# usb-rs485.net
KiCad netlist of a schematic drawn in EAGLE
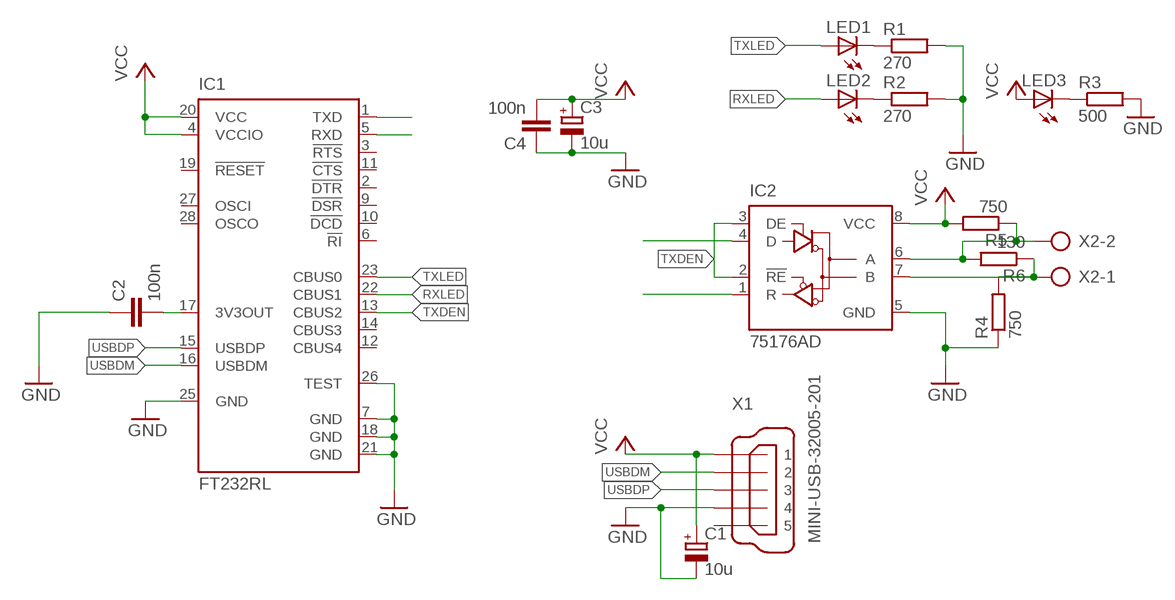
[diagram p0: schematic, sheet 1]

(export (version "E")
  (design (tool "Eeschema 10.0.6"))
  (components
    (comp (ref "C1")
      (value "10u")
      (footprint "eagle-import:PANASONIC_D")
      (libsource (lib "eagle-import") (part "CPOL-EUD"))
    )
    (comp (ref "C2")
      (value "100n")
      (footprint "eagle-import:C0805")
      (libsource (lib "eagle-import") (part "C-EUC0805"))
    )
    (comp (ref "C3")
      (value "10u")
      (footprint "eagle-import:PANASONIC_D")
      (libsource (lib "eagle-import") (part "CPOL-EUD"))
    )
    (comp (ref "C4")
      (value "100n")
      (footprint "eagle-import:C0805")
      (libsource (lib "eagle-import") (part "C-EUC0805"))
    )
    (comp (ref "IC1")
      (value "FT232RL")
      (footprint "eagle-import:SSOP28")
      (libsource (lib "eagle-import") (part "FT232RL"))
    )
    (comp (ref "IC2")
      (value "75176AD")
      (footprint "eagle-import:D_R-PDSO-G8")
      (libsource (lib "eagle-import") (part "75176AD"))
    )
    (comp (ref "LED1")
      (value "LEDSML0805")
      (footprint "eagle-import:SML0805")
      (libsource (lib "eagle-import") (part "LEDSML0805"))
    )
    (comp (ref "LED2")
      (value "LEDSML0805")
      (footprint "eagle-import:SML0805")
      (libsource (lib "eagle-import") (part "LEDSML0805"))
    )
    (comp (ref "LED3")
      (value "LEDSML0805")
      (footprint "eagle-import:SML0805")
      (libsource (lib "eagle-import") (part "LEDSML0805"))
    )
    (comp (ref "R1")
      (value "270")
      (footprint "eagle-import:R0805")
      (libsource (lib "eagle-import") (part "R-EU_R0805"))
    )
    (comp (ref "R2")
      (value "270")
      (footprint "eagle-import:R0805")
      (libsource (lib "eagle-import") (part "R-EU_R0805"))
    )
    (comp (ref "R3")
      (value "500")
      (footprint "eagle-import:R0805")
      (libsource (lib "eagle-import") (part "R-EU_R0805"))
    )
    (comp (ref "R4")
      (value "750")
      (footprint "eagle-import:R0805")
      (libsource (lib "eagle-import") (part "R-EU_R0805"))
    )
    (comp (ref "R5")
      (value "750")
      (footprint "eagle-import:R0805")
      (libsource (lib "eagle-import") (part "R-EU_R0805"))
    )
    (comp (ref "R6")
      (value "130")
      (footprint "eagle-import:R0805")
      (libsource (lib "eagle-import") (part "R-EU_R0805"))
    )
    (comp (ref "X1")
      (value "MINI-USB-32005-201")
      (footprint "eagle-import:32005-201")
      (libsource (lib "eagle-import") (part "MINI-USB-32005-201"))
    )
    (comp (ref "X2")
      (value "AK300/2")
      (footprint "eagle-import:AK300_2")
      (libsource (lib "eagle-import") (part "AK300/2"))
    )
  )
  (nets
    (net (code "1") (name "/RX") (class "Default")
      (node (ref "IC1") (pin "5") (pinfunction "RXD_5") (pintype "input"))
      (node (ref "IC2") (pin "1") (pinfunction "R_1") (pintype "input"))
    )
    (net (code "2") (name "/TX") (class "Default")
      (node (ref "IC1") (pin "1") (pinfunction "TXD_1") (pintype "output"))
      (node (ref "IC2") (pin "4") (pinfunction "D_4") (pintype "input"))
    )
    (net (code "3") (name "GND") (class "Default")
      (node (ref "C1") (pin "-") (pinfunction "-_-") (pintype "passive"))
      (node (ref "C2") (pin "1") (pinfunction "1_1") (pintype "passive"))
      (node (ref "C3") (pin "-") (pinfunction "-_-") (pintype "passive"))
      (node (ref "C4") (pin "1") (pinfunction "1_1") (pintype "passive"))
      (node (ref "IC1") (pin "18") (pinfunction "GND_18") (pintype "power_in"))
      (node (ref "IC1") (pin "21") (pinfunction "GND_21") (pintype "power_in"))
      (node (ref "IC1") (pin "25") (pinfunction "GND_25") (pintype "power_in"))
      (node (ref "IC1") (pin "26") (pinfunction "TEST_26") (pintype "input"))
      (node (ref "IC1") (pin "7") (pinfunction "GND_7") (pintype "power_in"))
      (node (ref "IC2") (pin "5") (pinfunction "GND_5") (pintype "power_in"))
      (node (ref "R1") (pin "2") (pinfunction "2_2") (pintype "passive"))
      (node (ref "R2") (pin "2") (pinfunction "2_2") (pintype "passive"))
      (node (ref "R3") (pin "2") (pinfunction "2_2") (pintype "passive"))
      (node (ref "R4") (pin "1") (pinfunction "1_1") (pintype "passive"))
      (node (ref "X1") (pin "4") (pinfunction "4_4") (pintype "passive"))
    )
    (net (code "4") (name "Net-(IC1-3V3OUT)") (class "Default")
      (node (ref "C2") (pin "2") (pinfunction "2_2") (pintype "passive"))
      (node (ref "IC1") (pin "17") (pinfunction "3V3OUT_17") (pintype "output"))
    )
    (net (code "5") (name "Net-(IC2-A)") (class "Default")
      (node (ref "IC2") (pin "6") (pinfunction "A_6") (pintype "output"))
      (node (ref "R5") (pin "1") (pinfunction "1_1") (pintype "passive"))
      (node (ref "R6") (pin "2") (pinfunction "2_2") (pintype "passive"))
      (node (ref "X2") (pin "2") (pinfunction "KL_2") (pintype "passive"))
    )
    (net (code "6") (name "Net-(IC2-B)") (class "Default")
      (node (ref "IC2") (pin "7") (pinfunction "B_7") (pintype "output"))
      (node (ref "R4") (pin "2") (pinfunction "2_2") (pintype "passive"))
      (node (ref "R6") (pin "1") (pinfunction "1_1") (pintype "passive"))
      (node (ref "X2") (pin "1") (pinfunction "KL_1") (pintype "passive"))
    )
    (net (code "7") (name "Net-(LED1-PadC)") (class "Default")
      (node (ref "LED1") (pin "C") (pinfunction "C_C") (pintype "passive"))
      (node (ref "R1") (pin "1") (pinfunction "1_1") (pintype "passive"))
    )
    (net (code "8") (name "Net-(LED2-PadC)") (class "Default")
      (node (ref "LED2") (pin "C") (pinfunction "C_C") (pintype "passive"))
      (node (ref "R2") (pin "1") (pinfunction "1_1") (pintype "passive"))
    )
    (net (code "9") (name "Net-(LED3-PadC)") (class "Default")
      (node (ref "LED3") (pin "C") (pinfunction "C_C") (pintype "passive"))
      (node (ref "R3") (pin "1") (pinfunction "1_1") (pintype "passive"))
    )
    (net (code "10") (name "RXLED") (class "Default")
      (node (ref "IC1") (pin "22") (pinfunction "CBUS1_22") (pintype "bidirectional"))
      (node (ref "LED2") (pin "A") (pinfunction "A_A") (pintype "passive"))
    )
    (net (code "11") (name "TXDEN") (class "Default")
      (node (ref "IC1") (pin "13") (pinfunction "CBUS2_13") (pintype "bidirectional"))
      (node (ref "IC2") (pin "2") (pinfunction "~{RE}_2") (pintype "input"))
      (node (ref "IC2") (pin "3") (pinfunction "DE_3") (pintype "input"))
    )
    (net (code "12") (name "TXLED") (class "Default")
      (node (ref "IC1") (pin "23") (pinfunction "CBUS0_23") (pintype "bidirectional"))
      (node (ref "LED1") (pin "A") (pinfunction "A_A") (pintype "passive"))
    )
    (net (code "13") (name "USBDM") (class "Default")
      (node (ref "IC1") (pin "16") (pinfunction "USBDM_16") (pintype "bidirectional"))
      (node (ref "X1") (pin "2") (pinfunction "2_2") (pintype "passive"))
    )
    (net (code "14") (name "USBDP") (class "Default")
      (node (ref "IC1") (pin "15") (pinfunction "USBDP_15") (pintype "bidirectional"))
      (node (ref "X1") (pin "3") (pinfunction "3_3") (pintype "passive"))
    )
    (net (code "15") (name "VCC") (class "Default")
      (node (ref "C1") (pin "+") (pinfunction "+_+") (pintype "passive"))
      (node (ref "C3") (pin "+") (pinfunction "+_+") (pintype "passive"))
      (node (ref "C4") (pin "2") (pinfunction "2_2") (pintype "passive"))
      (node (ref "IC1") (pin "20") (pinfunction "VCC_20") (pintype "power_in"))
      (node (ref "IC1") (pin "4") (pinfunction "VCCIO_4") (pintype "power_in"))
      (node (ref "IC2") (pin "8") (pinfunction "VCC_8") (pintype "power_in"))
      (node (ref "LED3") (pin "A") (pinfunction "A_A") (pintype "passive"))
      (node (ref "R5") (pin "2") (pinfunction "2_2") (pintype "passive"))
      (node (ref "X1") (pin "1") (pinfunction "1_1") (pintype "passive"))
    )
    (net (code "16") (name "unconnected-(IC1-CBUS3-Pad14)") (class "Default")
      (node (ref "IC1") (pin "14") (pinfunction "CBUS3_14") (pintype "bidirectional"))
    )
    (net (code "17") (name "unconnected-(IC1-CBUS4-Pad12)") (class "Default")
      (node (ref "IC1") (pin "12") (pinfunction "CBUS4_12") (pintype "bidirectional"))
    )
    (net (code "18") (name "unconnected-(IC1-OSCI-Pad27)") (class "Default")
      (node (ref "IC1") (pin "27") (pinfunction "OSCI_27") (pintype "input"))
    )
    (net (code "19") (name "unconnected-(IC1-OSCO-Pad28)") (class "Default")
      (node (ref "IC1") (pin "28") (pinfunction "OSCO_28") (pintype "output"))
    )
    (net (code "20") (name "unconnected-(IC1-~{CTS}-Pad11)") (class "Default")
      (node (ref "IC1") (pin "11") (pinfunction "~{CTS}_11") (pintype "input"))
    )
    (net (code "21") (name "unconnected-(IC1-~{DCD}-Pad10)") (class "Default")
      (node (ref "IC1") (pin "10") (pinfunction "~{DCD}_10") (pintype "input"))
    )
    (net (code "22") (name "unconnected-(IC1-~{DSR}-Pad9)") (class "Default")
      (node (ref "IC1") (pin "9") (pinfunction "~{DSR}_9") (pintype "input"))
    )
    (net (code "23") (name "unconnected-(IC1-~{DTR}-Pad2)") (class "Default")
      (node (ref "IC1") (pin "2") (pinfunction "~{DTR}_2") (pintype "output"))
    )
    (net (code "24") (name "unconnected-(IC1-~{RESET}-Pad19)") (class "Default")
      (node (ref "IC1") (pin "19") (pinfunction "~{RESET}_19") (pintype "input"))
    )
    (net (code "25") (name "unconnected-(IC1-~{RI}-Pad6)") (class "Default")
      (node (ref "IC1") (pin "6") (pinfunction "~{RI}_6") (pintype "input"))
    )
    (net (code "26") (name "unconnected-(IC1-~{RTS}-Pad3)") (class "Default")
      (node (ref "IC1") (pin "3") (pinfunction "~{RTS}_3") (pintype "output"))
    )
    (net (code "27") (name "unconnected-(X1-Pad5)") (class "Default")
      (node (ref "X1") (pin "5") (pinfunction "5_5") (pintype "passive"))
    )
  )
)
